# NIRGM_V8.net
KiCad netlist of a schematic drawn in EAGLE
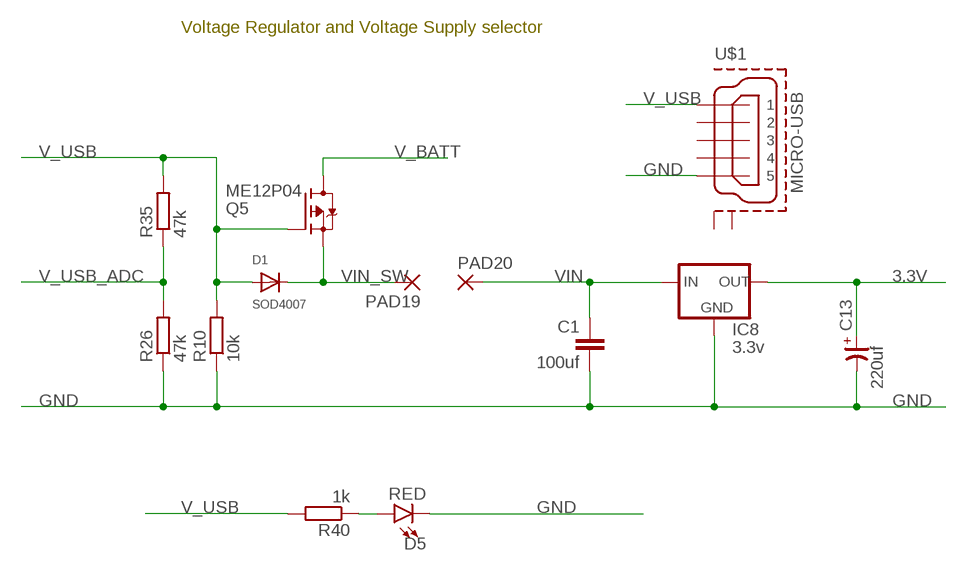
[diagram p0: schematic, sheet 1]
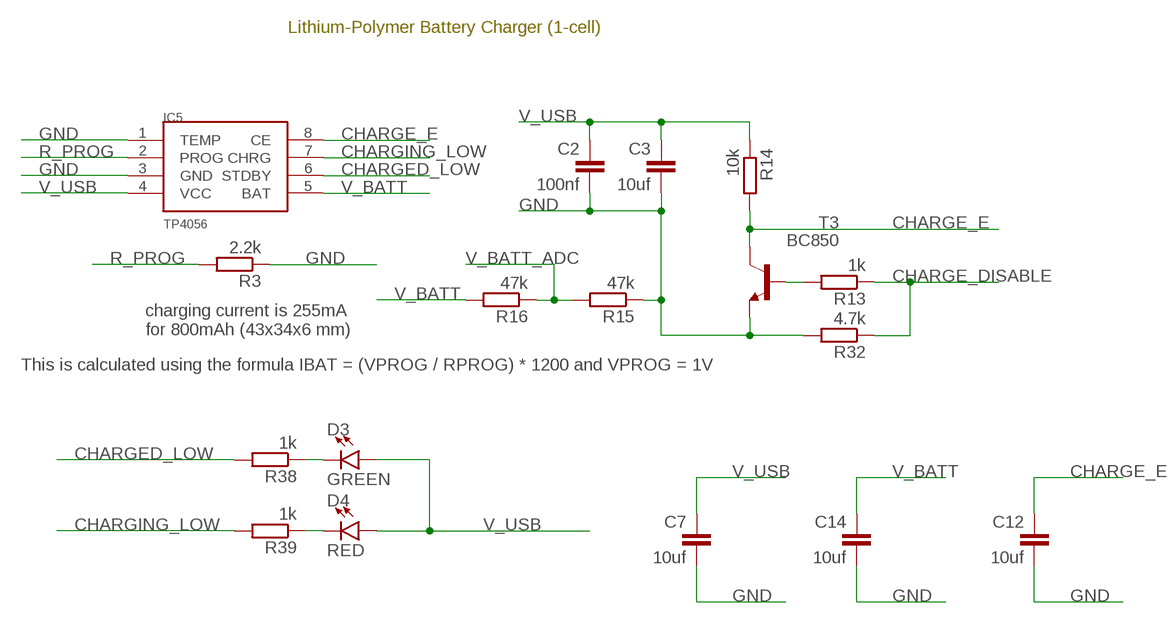
[diagram p1: schematic, sheet 2]
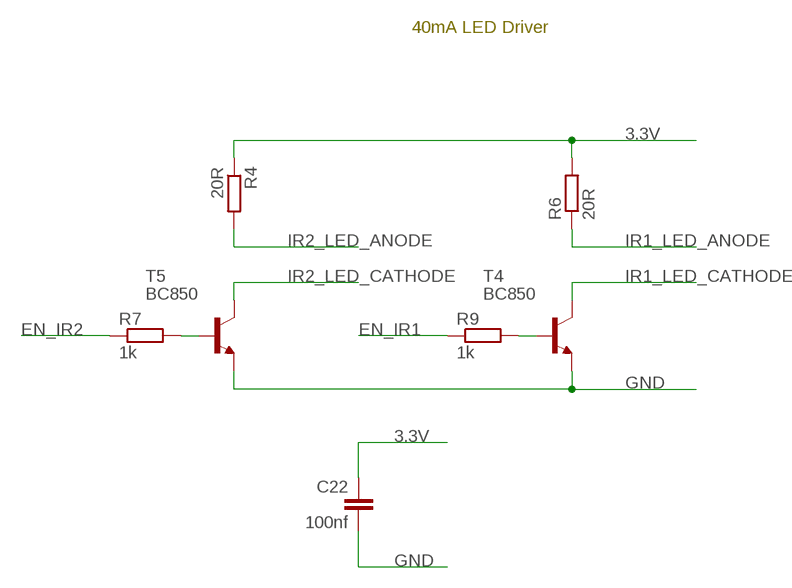
[diagram p2: schematic, sheet 3]
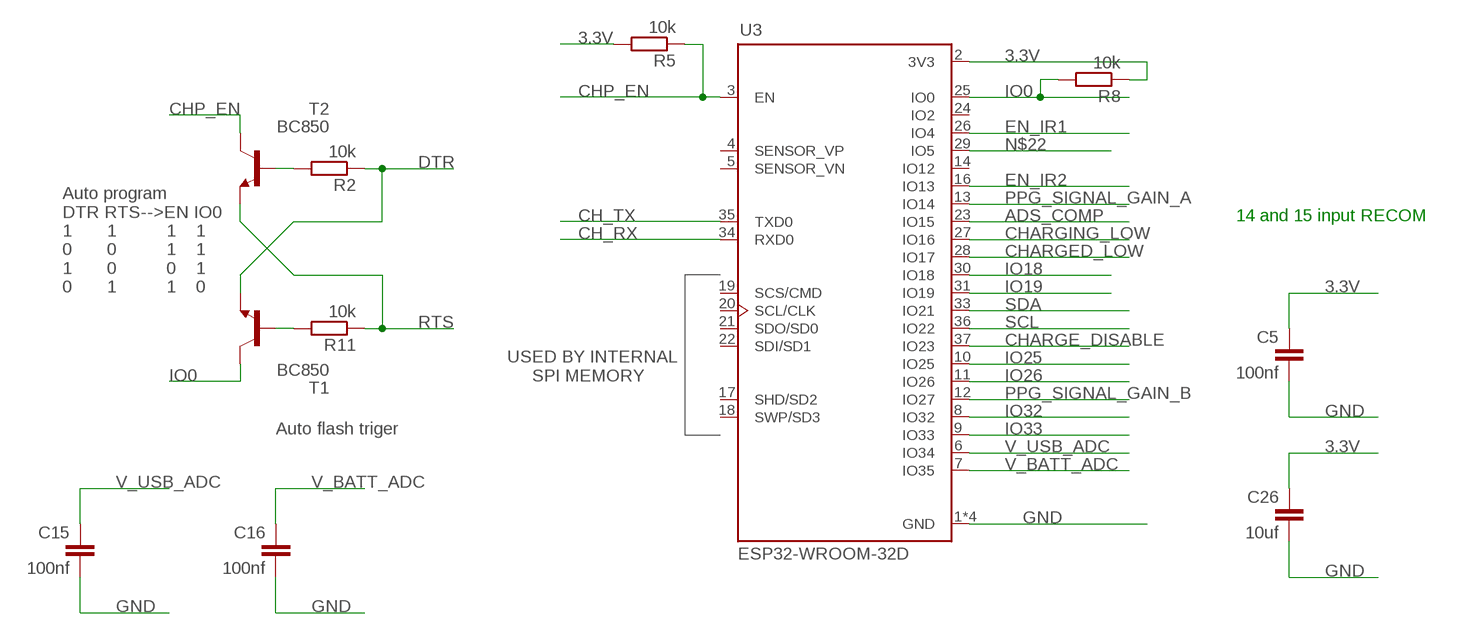
[diagram p3: schematic, sheet 4]
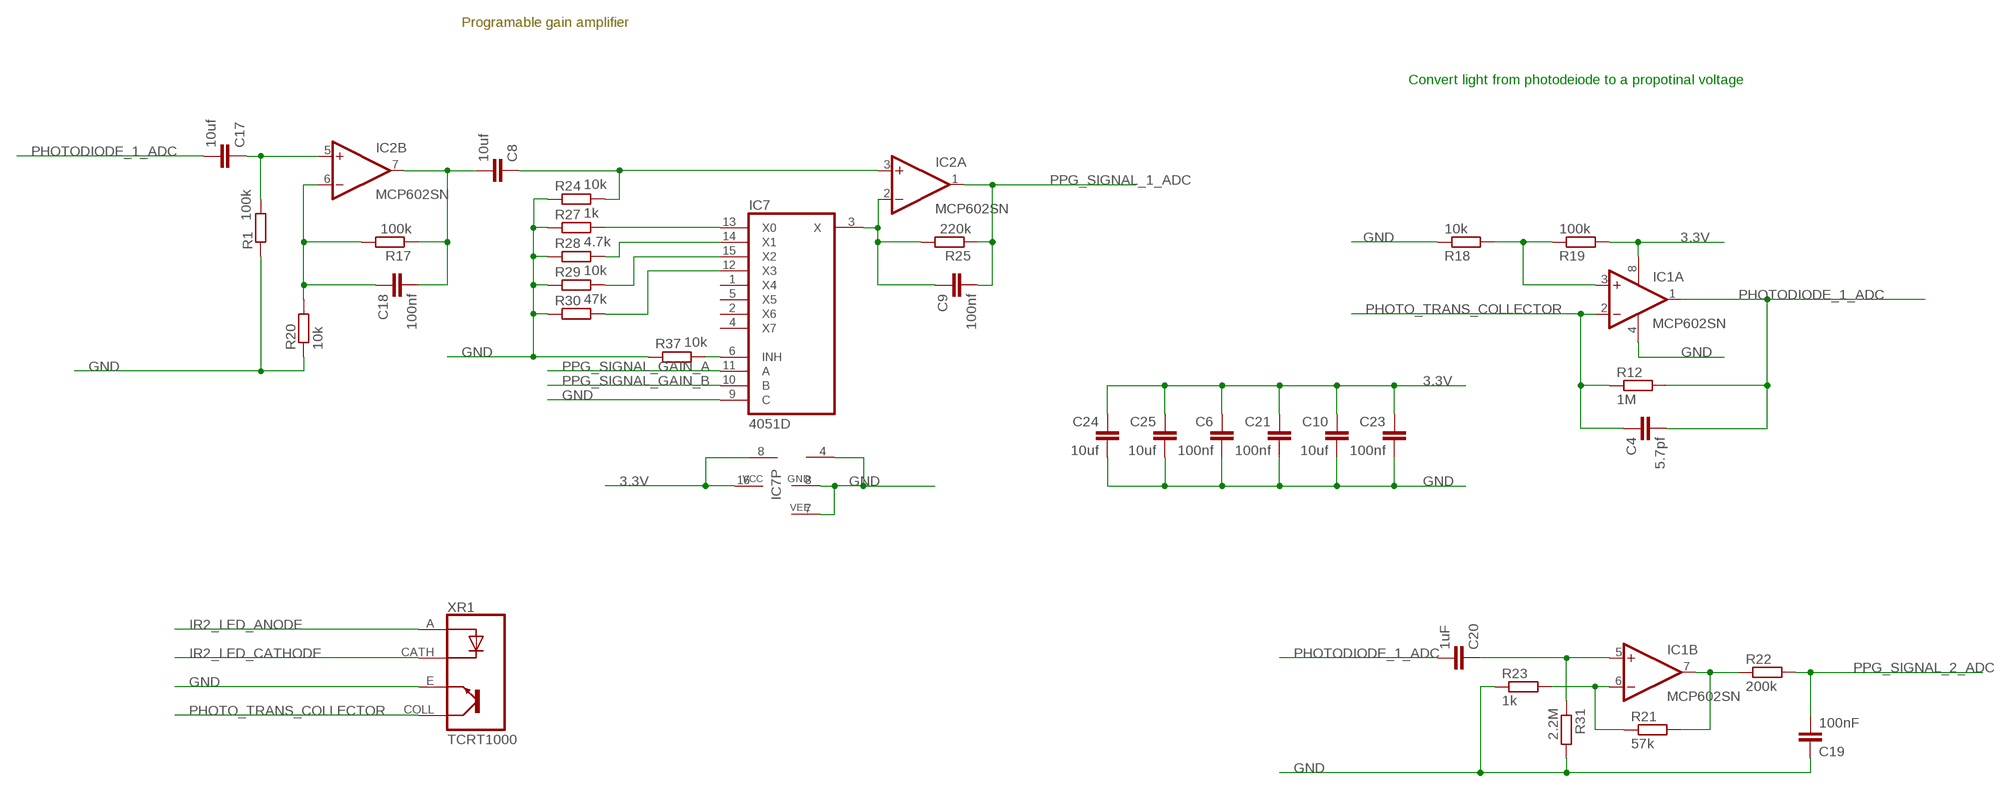
[diagram p4: schematic, sheet 5]
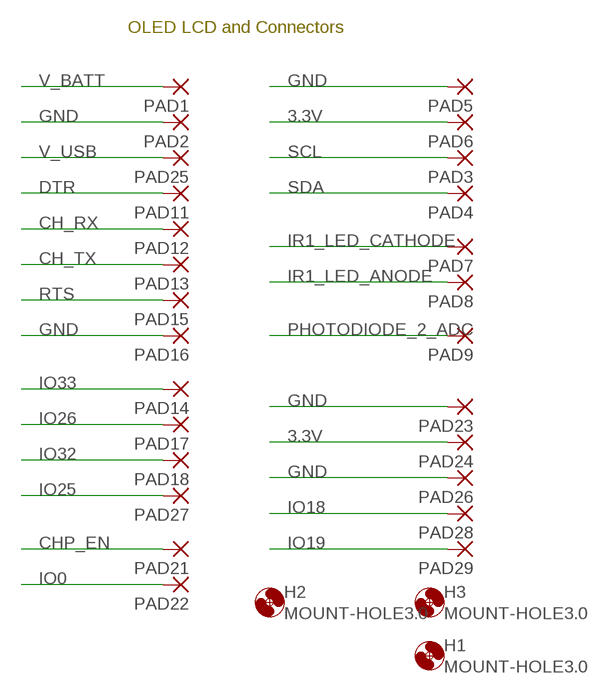
[diagram p5: schematic, sheet 6]
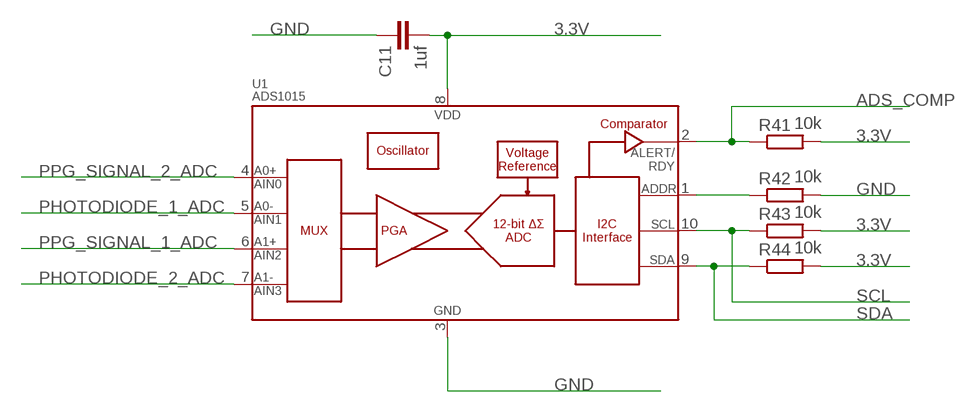
[diagram p6: schematic, sheet 7]

(export (version "E")
  (design (tool "Eeschema 10.0.6"))
  (components
    (comp (ref "C5")
      (value "100nf")
      (footprint "eagle-import:C1206K")
      (libsource (lib "eagle-import") (part "C-EUC1206K"))
    )
    (comp (ref "C15")
      (value "100nf")
      (footprint "eagle-import:C1206K")
      (libsource (lib "eagle-import") (part "C-EUC1206K"))
    )
    (comp (ref "C16")
      (value "100nf")
      (footprint "eagle-import:C1206K")
      (libsource (lib "eagle-import") (part "C-EUC1206K"))
    )
    (comp (ref "C26")
      (value "10uf")
      (footprint "eagle-import:C1206K")
      (libsource (lib "eagle-import") (part "C-EUC1206K"))
    )
    (comp (ref "R2")
      (value "10k")
      (footprint "eagle-import:R1206")
      (libsource (lib "eagle-import") (part "R-EU_R1206"))
    )
    (comp (ref "R5")
      (value "10k")
      (footprint "eagle-import:R1206")
      (libsource (lib "eagle-import") (part "R-EU_R1206"))
    )
    (comp (ref "R8")
      (value "10k")
      (footprint "eagle-import:R1206")
      (libsource (lib "eagle-import") (part "R-EU_R1206"))
    )
    (comp (ref "R11")
      (value "10k")
      (footprint "eagle-import:R1206")
      (libsource (lib "eagle-import") (part "R-EU_R1206"))
    )
    (comp (ref "T1")
      (value "BC850")
      (footprint "eagle-import:SOT23")
      (libsource (lib "eagle-import") (part "BC850"))
    )
    (comp (ref "T2")
      (value "BC850")
      (footprint "eagle-import:SOT23")
      (libsource (lib "eagle-import") (part "BC850"))
    )
    (comp (ref "U3")
      (value "ESP32-WROOM-32D")
      (footprint "eagle-import:MODULE_ESP32-WROOM-32D")
      (fields (field (name "MF") "Espressif Systems"))
      (libsource (lib "eagle-import") (part "ESP32-WROOM-32D"))
    )
    (comp (ref "C2")
      (value "100nf")
      (footprint "eagle-import:C1206K")
      (libsource (lib "eagle-import") (part "C-EUC1206K"))
    )
    (comp (ref "C3")
      (value "10uf")
      (footprint "eagle-import:C1206K")
      (libsource (lib "eagle-import") (part "C-EUC1206K"))
    )
    (comp (ref "C7")
      (value "10uf")
      (footprint "eagle-import:C1206K")
      (libsource (lib "eagle-import") (part "C-EUC1206K"))
    )
    (comp (ref "C12")
      (value "10uf")
      (footprint "eagle-import:C1206K")
      (libsource (lib "eagle-import") (part "C-EUC1206K"))
    )
    (comp (ref "C14")
      (value "10uf")
      (footprint "eagle-import:C1206K")
      (libsource (lib "eagle-import") (part "C-EUC1206K"))
    )
    (comp (ref "D3")
      (value "GREEN")
      (footprint "eagle-import:LED-1206")
      (libsource (lib "eagle-import") (part "LED-GREEN1206"))
    )
    (comp (ref "D4")
      (value "RED")
      (footprint "eagle-import:LED-1206")
      (libsource (lib "eagle-import") (part "LED-GREEN1206"))
    )
    (comp (ref "IC5")
      (value "TP4056")
      (footprint "eagle-import:SOP-8")
      (libsource (lib "eagle-import") (part "TP4056"))
    )
    (comp (ref "R3")
      (value "2.2k")
      (footprint "eagle-import:R1206")
      (libsource (lib "eagle-import") (part "R-EU_R1206"))
    )
    (comp (ref "R13")
      (value "1k")
      (footprint "eagle-import:R1206")
      (libsource (lib "eagle-import") (part "R-EU_R1206"))
    )
    (comp (ref "R14")
      (value "10k")
      (footprint "eagle-import:R1206")
      (libsource (lib "eagle-import") (part "R-EU_R1206"))
    )
    (comp (ref "R15")
      (value "47k")
      (footprint "eagle-import:R1206")
      (libsource (lib "eagle-import") (part "R-EU_R1206"))
    )
    (comp (ref "R16")
      (value "47k")
      (footprint "eagle-import:R1206")
      (libsource (lib "eagle-import") (part "R-EU_R1206"))
    )
    (comp (ref "R32")
      (value "4.7k")
      (footprint "eagle-import:R1206")
      (libsource (lib "eagle-import") (part "R-EU_R1206"))
    )
    (comp (ref "R38")
      (value "1k")
      (footprint "eagle-import:R1206")
      (libsource (lib "eagle-import") (part "R-EU_R1206"))
    )
    (comp (ref "R39")
      (value "1k")
      (footprint "eagle-import:R1206")
      (libsource (lib "eagle-import") (part "R-EU_R1206"))
    )
    (comp (ref "T3")
      (value "BC850")
      (footprint "eagle-import:SOT23")
      (libsource (lib "eagle-import") (part "BC850"))
    )
    (comp (ref "H1")
      (value "MOUNT-HOLE3.0")
      (footprint "eagle-import:3,0")
      (libsource (lib "eagle-import") (part "MOUNT-HOLE3.0"))
    )
    (comp (ref "H2")
      (value "MOUNT-HOLE3.0")
      (footprint "eagle-import:3,0")
      (libsource (lib "eagle-import") (part "MOUNT-HOLE3.0"))
    )
    (comp (ref "H3")
      (value "MOUNT-HOLE3.0")
      (footprint "eagle-import:3,0")
      (libsource (lib "eagle-import") (part "MOUNT-HOLE3.0"))
    )
    (comp (ref "PAD1")
      (value "WIREPADSMD5-2,5")
      (footprint "eagle-import:5-2,5")
      (libsource (lib "eagle-import") (part "WIREPADSMD5-2,5"))
    )
    (comp (ref "PAD2")
      (value "WIREPADSMD5-2,5")
      (footprint "eagle-import:5-2,5")
      (libsource (lib "eagle-import") (part "WIREPADSMD5-2,5"))
    )
    (comp (ref "PAD3")
      (value "SMD2")
      (footprint "eagle-import:SMD1,27-2,54")
      (libsource (lib "eagle-import") (part "SMD2"))
    )
    (comp (ref "PAD4")
      (value "SMD2")
      (footprint "eagle-import:SMD1,27-2,54")
      (libsource (lib "eagle-import") (part "SMD2"))
    )
    (comp (ref "PAD5")
      (value "SMD2")
      (footprint "eagle-import:SMD1,27-2,54")
      (libsource (lib "eagle-import") (part "SMD2"))
    )
    (comp (ref "PAD6")
      (value "SMD2")
      (footprint "eagle-import:SMD1,27-2,54")
      (libsource (lib "eagle-import") (part "SMD2"))
    )
    (comp (ref "PAD7")
      (value "SMD2")
      (footprint "eagle-import:SMD1,27-2,54")
      (libsource (lib "eagle-import") (part "SMD2"))
    )
    (comp (ref "PAD8")
      (value "SMD2")
      (footprint "eagle-import:SMD1,27-2,54")
      (libsource (lib "eagle-import") (part "SMD2"))
    )
    (comp (ref "PAD9")
      (value "SMD2")
      (footprint "eagle-import:SMD1,27-2,54")
      (libsource (lib "eagle-import") (part "SMD2"))
    )
    (comp (ref "PAD11")
      (value "SMD2")
      (footprint "eagle-import:SMD1,27-2,54")
      (libsource (lib "eagle-import") (part "SMD2"))
    )
    (comp (ref "PAD12")
      (value "SMD2")
      (footprint "eagle-import:SMD1,27-2,54")
      (libsource (lib "eagle-import") (part "SMD2"))
    )
    (comp (ref "PAD13")
      (value "SMD2")
      (footprint "eagle-import:SMD1,27-2,54")
      (libsource (lib "eagle-import") (part "SMD2"))
    )
    (comp (ref "PAD14")
      (value "SMD2")
      (footprint "eagle-import:SMD1,27-2,54")
      (libsource (lib "eagle-import") (part "SMD2"))
    )
    (comp (ref "PAD15")
      (value "SMD2")
      (footprint "eagle-import:SMD1,27-2,54")
      (libsource (lib "eagle-import") (part "SMD2"))
    )
    (comp (ref "PAD16")
      (value "SMD2")
      (footprint "eagle-import:SMD1,27-2,54")
      (libsource (lib "eagle-import") (part "SMD2"))
    )
    (comp (ref "PAD17")
      (value "SMD2")
      (footprint "eagle-import:SMD1,27-2,54")
      (libsource (lib "eagle-import") (part "SMD2"))
    )
    (comp (ref "PAD18")
      (value "SMD2")
      (footprint "eagle-import:SMD1,27-2,54")
      (libsource (lib "eagle-import") (part "SMD2"))
    )
    (comp (ref "PAD21")
      (value "SMD2")
      (footprint "eagle-import:SMD1,27-2,54")
      (libsource (lib "eagle-import") (part "SMD2"))
    )
    (comp (ref "PAD22")
      (value "SMD2")
      (footprint "eagle-import:SMD1,27-2,54")
      (libsource (lib "eagle-import") (part "SMD2"))
    )
    (comp (ref "PAD23")
      (value "SMD2")
      (footprint "eagle-import:SMD1,27-2,54")
      (libsource (lib "eagle-import") (part "SMD2"))
    )
    (comp (ref "PAD24")
      (value "SMD2")
      (footprint "eagle-import:SMD1,27-2,54")
      (libsource (lib "eagle-import") (part "SMD2"))
    )
    (comp (ref "PAD25")
      (value "SMD2")
      (footprint "eagle-import:SMD1,27-2,54")
      (libsource (lib "eagle-import") (part "SMD2"))
    )
    (comp (ref "PAD26")
      (value "SMD2")
      (footprint "eagle-import:SMD1,27-2,54")
      (libsource (lib "eagle-import") (part "SMD2"))
    )
    (comp (ref "PAD27")
      (value "SMD2")
      (footprint "eagle-import:SMD1,27-2,54")
      (libsource (lib "eagle-import") (part "SMD2"))
    )
    (comp (ref "PAD28")
      (value "SMD2")
      (footprint "eagle-import:SMD1,27-2,54")
      (libsource (lib "eagle-import") (part "SMD2"))
    )
    (comp (ref "PAD29")
      (value "SMD2")
      (footprint "eagle-import:SMD1,27-2,54")
      (libsource (lib "eagle-import") (part "SMD2"))
    )
    (comp (ref "C4")
      (value "5.7pf")
      (footprint "eagle-import:C1206K")
      (libsource (lib "eagle-import") (part "C-EUC1206K"))
    )
    (comp (ref "C6")
      (value "100nf")
      (footprint "eagle-import:C1206K")
      (libsource (lib "eagle-import") (part "C-EUC1206K"))
    )
    (comp (ref "C8")
      (value "10uf")
      (footprint "eagle-import:C1206K")
      (libsource (lib "eagle-import") (part "C-EUC1206K"))
    )
    (comp (ref "C9")
      (value "100nf")
      (footprint "eagle-import:C1206K")
      (libsource (lib "eagle-import") (part "C-EUC1206K"))
    )
    (comp (ref "C10")
      (value "10uf")
      (footprint "eagle-import:C1206K")
      (libsource (lib "eagle-import") (part "C-EUC1206K"))
    )
    (comp (ref "C17")
      (value "10uf")
      (footprint "eagle-import:C1206K")
      (libsource (lib "eagle-import") (part "C-EUC1206K"))
    )
    (comp (ref "C18")
      (value "100nf")
      (footprint "eagle-import:C1206K")
      (libsource (lib "eagle-import") (part "C-EUC1206K"))
    )
    (comp (ref "C19")
      (value "100nF")
      (footprint "eagle-import:C1206K")
      (libsource (lib "eagle-import") (part "C-EUC1206K"))
    )
    (comp (ref "C20")
      (value "1uF")
      (footprint "eagle-import:C1206K")
      (libsource (lib "eagle-import") (part "C-EUC1206K"))
    )
    (comp (ref "C21")
      (value "100nf")
      (footprint "eagle-import:C1206K")
      (libsource (lib "eagle-import") (part "C-EUC1206K"))
    )
    (comp (ref "C23")
      (value "100nf")
      (footprint "eagle-import:C1206K")
      (libsource (lib "eagle-import") (part "C-EUC1206K"))
    )
    (comp (ref "C24")
      (value "10uf")
      (footprint "eagle-import:C1206K")
      (libsource (lib "eagle-import") (part "C-EUC1206K"))
    )
    (comp (ref "C25")
      (value "10uf")
      (footprint "eagle-import:C1206K")
      (libsource (lib "eagle-import") (part "C-EUC1206K"))
    )
    (comp (ref "IC1")
      (value "MCP602SN")
      (footprint "eagle-import:SO08")
      (libsource (lib "eagle-import") (part "linear_262_MCP602SN"))
    )
    (comp (ref "IC2")
      (value "MCP602SN")
      (footprint "eagle-import:SO08")
      (libsource (lib "eagle-import") (part "MCP602SN"))
    )
    (comp (ref "IC7")
      (value "4051D")
      (footprint "eagle-import:SO16")
      (libsource (lib "eagle-import") (part "4051D"))
    )
    (comp (ref "R1")
      (value "100k")
      (footprint "eagle-import:R1206")
      (libsource (lib "eagle-import") (part "R-EU_R1206"))
    )
    (comp (ref "R12")
      (value "1M")
      (footprint "eagle-import:R1206")
      (libsource (lib "eagle-import") (part "R-EU_R1206"))
    )
    (comp (ref "R17")
      (value "100k")
      (footprint "eagle-import:R1206")
      (libsource (lib "eagle-import") (part "R-EU_R1206"))
    )
    (comp (ref "R18")
      (value "10k")
      (footprint "eagle-import:R1206")
      (libsource (lib "eagle-import") (part "R-EU_R1206"))
    )
    (comp (ref "R19")
      (value "100k")
      (footprint "eagle-import:R1206")
      (libsource (lib "eagle-import") (part "R-EU_R1206"))
    )
    (comp (ref "R20")
      (value "10k")
      (footprint "eagle-import:R1206")
      (libsource (lib "eagle-import") (part "R-EU_R1206"))
    )
    (comp (ref "R21")
      (value "57k")
      (footprint "eagle-import:R1206")
      (libsource (lib "eagle-import") (part "R-EU_R1206"))
    )
    (comp (ref "R22")
      (value "200k")
      (footprint "eagle-import:R1206")
      (libsource (lib "eagle-import") (part "R-EU_R1206"))
    )
    (comp (ref "R23")
      (value "1k")
      (footprint "eagle-import:R1206")
      (libsource (lib "eagle-import") (part "R-EU_R1206"))
    )
    (comp (ref "R24")
      (value "10k")
      (footprint "eagle-import:R1206")
      (libsource (lib "eagle-import") (part "R-EU_R1206"))
    )
    (comp (ref "R25")
      (value "220k")
      (footprint "eagle-import:R1206")
      (libsource (lib "eagle-import") (part "R-EU_R1206"))
    )
    (comp (ref "R27")
      (value "1k")
      (footprint "eagle-import:R1206")
      (libsource (lib "eagle-import") (part "R-EU_R1206"))
    )
    (comp (ref "R28")
      (value "4.7k")
      (footprint "eagle-import:R1206")
      (libsource (lib "eagle-import") (part "R-EU_R1206"))
    )
    (comp (ref "R29")
      (value "10k")
      (footprint "eagle-import:R1206")
      (libsource (lib "eagle-import") (part "R-EU_R1206"))
    )
    (comp (ref "R30")
      (value "47k")
      (footprint "eagle-import:R1206")
      (libsource (lib "eagle-import") (part "R-EU_R1206"))
    )
    (comp (ref "R31")
      (value "2.2M")
      (footprint "eagle-import:R1206")
      (libsource (lib "eagle-import") (part "R-EU_R1206"))
    )
    (comp (ref "R37")
      (value "10k")
      (footprint "eagle-import:R1206")
      (libsource (lib "eagle-import") (part "R-EU_R1206"))
    )
    (comp (ref "XR1")
      (value "TCRT1000")
      (footprint "eagle-import:XDCR_TCRT1000")
      (fields (field (name "MF") "Vishay"))
      (libsource (lib "eagle-import") (part "TCRT1000"))
    )
    (comp (ref "C22")
      (value "100nf")
      (footprint "eagle-import:C1206K")
      (libsource (lib "eagle-import") (part "C-EUC1206K"))
    )
    (comp (ref "R4")
      (value "20R")
      (footprint "eagle-import:R1206")
      (libsource (lib "eagle-import") (part "R-EU_R1206"))
    )
    (comp (ref "R6")
      (value "20R")
      (footprint "eagle-import:R1206")
      (libsource (lib "eagle-import") (part "R-EU_R1206"))
    )
    (comp (ref "R7")
      (value "1k")
      (footprint "eagle-import:R1206")
      (libsource (lib "eagle-import") (part "R-EU_R1206"))
    )
    (comp (ref "R9")
      (value "1k")
      (footprint "eagle-import:R1206")
      (libsource (lib "eagle-import") (part "R-EU_R1206"))
    )
    (comp (ref "T4")
      (value "BC850")
      (footprint "eagle-import:SOT23")
      (libsource (lib "eagle-import") (part "BC850"))
    )
    (comp (ref "T5")
      (value "BC850")
      (footprint "eagle-import:SOT23")
      (libsource (lib "eagle-import") (part "BC850"))
    )
    (comp (ref "C11")
      (value "1uf")
      (footprint "eagle-import:C1206K")
      (libsource (lib "eagle-import") (part "C-EUC1206K"))
    )
    (comp (ref "R41")
      (value "10k")
      (footprint "eagle-import:R1206")
      (libsource (lib "eagle-import") (part "R-EU_R1206"))
    )
    (comp (ref "R42")
      (value "10k")
      (footprint "eagle-import:R1206")
      (libsource (lib "eagle-import") (part "R-EU_R1206"))
    )
    (comp (ref "R43")
      (value "10k")
      (footprint "eagle-import:R1206")
      (libsource (lib "eagle-import") (part "R-EU_R1206"))
    )
    (comp (ref "R44")
      (value "10k")
      (footprint "eagle-import:R1206")
      (libsource (lib "eagle-import") (part "R-EU_R1206"))
    )
    (comp (ref "U1")
      (value "ADS1015")
      (footprint "eagle-import:MSOP10")
      (libsource (lib "eagle-import") (part "ADS1015"))
    )
    (comp (ref "C1")
      (value "100uf")
      (footprint "eagle-import:C1206K")
      (libsource (lib "eagle-import") (part "C-EUC1206K"))
    )
    (comp (ref "C13")
      (value "220uf")
      (footprint "eagle-import:7343_T")
      (libsource (lib "eagle-import") (part "CP-7343"))
    )
    (comp (ref "D1")
      (value "SOD4007")
      (footprint "eagle-import:SOD-123FL")
      (libsource (lib "eagle-import") (part "DIODE_SOD-123FL"))
    )
    (comp (ref "D5")
      (value "RED")
      (footprint "eagle-import:LED-1206")
      (libsource (lib "eagle-import") (part "LED-GREEN1206"))
    )
    (comp (ref "IC8")
      (value "3.3v")
      (footprint "eagle-import:TO252")
      (libsource (lib "eagle-import") (part "LM1117TO252"))
    )
    (comp (ref "PAD19")
      (value "SMD2")
      (footprint "eagle-import:SMD1,27-2,54")
      (libsource (lib "eagle-import") (part "SMD2"))
    )
    (comp (ref "PAD20")
      (value "SMD2")
      (footprint "eagle-import:SMD1,27-2,54")
      (libsource (lib "eagle-import") (part "SMD2"))
    )
    (comp (ref "Q5")
      (value "ME12P04")
      (footprint "eagle-import:TO252")
      (libsource (lib "eagle-import") (part "FDD4141TO252"))
    )
    (comp (ref "R10")
      (value "10k")
      (footprint "eagle-import:R1206")
      (libsource (lib "eagle-import") (part "R-EU_R1206"))
    )
    (comp (ref "R26")
      (value "47k")
      (footprint "eagle-import:R1206")
      (libsource (lib "eagle-import") (part "R-EU_R1206"))
    )
    (comp (ref "R35")
      (value "47k")
      (footprint "eagle-import:R1206")
      (libsource (lib "eagle-import") (part "R-EU_R1206"))
    )
    (comp (ref "R40")
      (value "1k")
      (footprint "eagle-import:R1206")
      (libsource (lib "eagle-import") (part "R-EU_R1206"))
    )
    (comp (ref "U$1")
      (value "MICRO-USB")
      (footprint "eagle-import:47589-0001")
      (libsource (lib "eagle-import") (part "MICRO-USB-RECEPTACLE47589-0001"))
    )
  )
  (nets
    (net (code "1") (name "3.3V") (class "Default")
      (node (ref "C10") (pin "1") (pinfunction "1_1") (pintype "passive"))
      (node (ref "C11") (pin "2") (pinfunction "2_2") (pintype "passive"))
      (node (ref "C13") (pin "+") (pinfunction "+_+") (pintype "passive"))
      (node (ref "C21") (pin "1") (pinfunction "1_1") (pintype "passive"))
      (node (ref "C22") (pin "1") (pinfunction "1_1") (pintype "passive"))
      (node (ref "C23") (pin "1") (pinfunction "1_1") (pintype "passive"))
      (node (ref "C24") (pin "1") (pinfunction "1_1") (pintype "passive"))
      (node (ref "C25") (pin "1") (pinfunction "1_1") (pintype "passive"))
      (node (ref "C26") (pin "1") (pinfunction "1_1") (pintype "passive"))
      (node (ref "C5") (pin "1") (pinfunction "1_1") (pintype "passive"))
      (node (ref "C6") (pin "1") (pinfunction "1_1") (pintype "passive"))
      (node (ref "IC1") (pin "8") (pinfunction "V+_8") (pintype "power_in"))
      (node (ref "IC2") (pin "8") (pinfunction "V+_8") (pintype "power_in"))
      (node (ref "IC7") (pin "16") (pinfunction "VCC_16") (pintype "power_in"))
      (node (ref "IC8") (pin "3") (pinfunction "OUT_3") (pintype "passive"))
      (node (ref "PAD24") (pin "1") (pinfunction "P_1") (pintype "passive"))
      (node (ref "PAD6") (pin "1") (pinfunction "P_1") (pintype "passive"))
      (node (ref "R19") (pin "2") (pinfunction "2_2") (pintype "passive"))
      (node (ref "R4") (pin "1") (pinfunction "1_1") (pintype "passive"))
      (node (ref "R41") (pin "2") (pinfunction "2_2") (pintype "passive"))
      (node (ref "R43") (pin "2") (pinfunction "2_2") (pintype "passive"))
      (node (ref "R44") (pin "2") (pinfunction "2_2") (pintype "passive"))
      (node (ref "R5") (pin "2") (pinfunction "2_2") (pintype "passive"))
      (node (ref "R6") (pin "2") (pinfunction "2_2") (pintype "passive"))
      (node (ref "R8") (pin "1") (pinfunction "1_1") (pintype "passive"))
      (node (ref "U1") (pin "8") (pinfunction "VDD_8") (pintype "bidirectional"))
      (node (ref "U3") (pin "2") (pinfunction "3V3_2") (pintype "power_in"))
    )
    (net (code "2") (name "ADS_COMP") (class "Default")
      (node (ref "R41") (pin "1") (pinfunction "1_1") (pintype "passive"))
      (node (ref "U1") (pin "2") (pinfunction "ALERT/RDY_2") (pintype "bidirectional"))
      (node (ref "U3") (pin "23") (pinfunction "IO15_23") (pintype "bidirectional"))
    )
    (net (code "3") (name "CHARGED_LOW") (class "Default")
      (node (ref "IC5") (pin "6") (pinfunction "STDBY_6") (pintype "bidirectional"))
      (node (ref "R38") (pin "2") (pinfunction "2_2") (pintype "passive"))
      (node (ref "U3") (pin "28") (pinfunction "IO17_28") (pintype "bidirectional"))
    )
    (net (code "4") (name "CHARGE_DISABLE") (class "Default")
      (node (ref "R13") (pin "1") (pinfunction "1_1") (pintype "passive"))
      (node (ref "R32") (pin "1") (pinfunction "1_1") (pintype "passive"))
      (node (ref "U3") (pin "37") (pinfunction "IO23_37") (pintype "bidirectional"))
    )
    (net (code "5") (name "CHARGE_E") (class "Default")
      (node (ref "C12") (pin "1") (pinfunction "1_1") (pintype "passive"))
      (node (ref "IC5") (pin "8") (pinfunction "CE_8") (pintype "bidirectional"))
      (node (ref "R14") (pin "2") (pinfunction "2_2") (pintype "passive"))
      (node (ref "T3") (pin "3") (pinfunction "C_3") (pintype "passive"))
    )
    (net (code "6") (name "CHARGING_LOW") (class "Default")
      (node (ref "IC5") (pin "7") (pinfunction "CHRG_7") (pintype "bidirectional"))
      (node (ref "R39") (pin "2") (pinfunction "2_2") (pintype "passive"))
      (node (ref "U3") (pin "27") (pinfunction "IO16_27") (pintype "bidirectional"))
    )
    (net (code "7") (name "CHP_EN") (class "Default")
      (node (ref "PAD21") (pin "1") (pinfunction "P_1") (pintype "passive"))
      (node (ref "R5") (pin "1") (pinfunction "1_1") (pintype "passive"))
      (node (ref "T2") (pin "3") (pinfunction "C_3") (pintype "passive"))
      (node (ref "U3") (pin "3") (pinfunction "EN_3") (pintype "input"))
    )
    (net (code "8") (name "CH_RX") (class "Default")
      (node (ref "PAD12") (pin "1") (pinfunction "P_1") (pintype "passive"))
      (node (ref "U3") (pin "34") (pinfunction "RXD0_34") (pintype "bidirectional"))
    )
    (net (code "9") (name "CH_TX") (class "Default")
      (node (ref "PAD13") (pin "1") (pinfunction "P_1") (pintype "passive"))
      (node (ref "U3") (pin "35") (pinfunction "TXD0_35") (pintype "bidirectional"))
    )
    (net (code "10") (name "DTR") (class "Default")
      (node (ref "PAD11") (pin "1") (pinfunction "P_1") (pintype "passive"))
      (node (ref "R2") (pin "1") (pinfunction "1_1") (pintype "passive"))
      (node (ref "T1") (pin "2") (pinfunction "E_2") (pintype "passive"))
    )
    (net (code "11") (name "EN_IR1") (class "Default")
      (node (ref "R9") (pin "1") (pinfunction "1_1") (pintype "passive"))
      (node (ref "U3") (pin "26") (pinfunction "IO4_26") (pintype "bidirectional"))
    )
    (net (code "12") (name "EN_IR2") (class "Default")
      (node (ref "R7") (pin "1") (pinfunction "1_1") (pintype "passive"))
      (node (ref "U3") (pin "16") (pinfunction "IO13_16") (pintype "bidirectional"))
    )
    (net (code "13") (name "GND") (class "Default")
      (node (ref "C1") (pin "2") (pinfunction "2_2") (pintype "passive"))
      (node (ref "C10") (pin "2") (pinfunction "2_2") (pintype "passive"))
      (node (ref "C11") (pin "1") (pinfunction "1_1") (pintype "passive"))
      (node (ref "C12") (pin "2") (pinfunction "2_2") (pintype "passive"))
      (node (ref "C13") (pin "-") (pinfunction "-_-") (pintype "passive"))
      (node (ref "C14") (pin "2") (pinfunction "2_2") (pintype "passive"))
      (node (ref "C15") (pin "2") (pinfunction "2_2") (pintype "passive"))
      (node (ref "C16") (pin "2") (pinfunction "2_2") (pintype "passive"))
      (node (ref "C19") (pin "1") (pinfunction "1_1") (pintype "passive"))
      (node (ref "C2") (pin "2") (pinfunction "2_2") (pintype "passive"))
      (node (ref "C21") (pin "2") (pinfunction "2_2") (pintype "passive"))
      (node (ref "C22") (pin "2") (pinfunction "2_2") (pintype "passive"))
      (node (ref "C23") (pin "2") (pinfunction "2_2") (pintype "passive"))
      (node (ref "C24") (pin "2") (pinfunction "2_2") (pintype "passive"))
      (node (ref "C25") (pin "2") (pinfunction "2_2") (pintype "passive"))
      (node (ref "C26") (pin "2") (pinfunction "2_2") (pintype "passive"))
      (node (ref "C3") (pin "2") (pinfunction "2_2") (pintype "passive"))
      (node (ref "C5") (pin "2") (pinfunction "2_2") (pintype "passive"))
      (node (ref "C6") (pin "2") (pinfunction "2_2") (pintype "passive"))
      (node (ref "C7") (pin "2") (pinfunction "2_2") (pintype "passive"))
      (node (ref "D5") (pin "C") (pinfunction "C_C") (pintype "passive"))
      (node (ref "IC1") (pin "4") (pinfunction "V-_4") (pintype "power_in"))
      (node (ref "IC2") (pin "4") (pinfunction "V-_4") (pintype "power_in"))
      (node (ref "IC5") (pin "1") (pinfunction "TEMP_1") (pintype "bidirectional"))
      (node (ref "IC5") (pin "3") (pinfunction "GND_3") (pintype "bidirectional"))
      (node (ref "IC7") (pin "7") (pinfunction "VEE_7") (pintype "power_in"))
      (node (ref "IC7") (pin "8") (pinfunction "GND_8") (pintype "power_in"))
      (node (ref "IC7") (pin "9") (pinfunction "C_9") (pintype "input"))
      (node (ref "IC8") (pin "1") (pinfunction "GND_1") (pintype "input"))
      (node (ref "PAD16") (pin "1") (pinfunction "P_1") (pintype "passive"))
      (node (ref "PAD2") (pin "1") (pinfunction "P_1") (pintype "passive"))
      (node (ref "PAD23") (pin "1") (pinfunction "P_1") (pintype "passive"))
      (node (ref "PAD26") (pin "1") (pinfunction "P_1") (pintype "passive"))
      (node (ref "PAD5") (pin "1") (pinfunction "P_1") (pintype "passive"))
      (node (ref "R1") (pin "1") (pinfunction "1_1") (pintype "passive"))
      (node (ref "R10") (pin "1") (pinfunction "1_1") (pintype "passive"))
      (node (ref "R15") (pin "1") (pinfunction "1_1") (pintype "passive"))
      (node (ref "R18") (pin "1") (pinfunction "1_1") (pintype "passive"))
      (node (ref "R20") (pin "1") (pinfunction "1_1") (pintype "passive"))
      (node (ref "R23") (pin "1") (pinfunction "1_1") (pintype "passive"))
      (node (ref "R24") (pin "1") (pinfunction "1_1") (pintype "passive"))
      (node (ref "R26") (pin "1") (pinfunction "1_1") (pintype "passive"))
      (node (ref "R27") (pin "1") (pinfunction "1_1") (pintype "passive"))
      (node (ref "R28") (pin "1") (pinfunction "1_1") (pintype "passive"))
      (node (ref "R29") (pin "1") (pinfunction "1_1") (pintype "passive"))
      (node (ref "R3") (pin "1") (pinfunction "1_1") (pintype "passive"))
      (node (ref "R30") (pin "1") (pinfunction "1_1") (pintype "passive"))
      (node (ref "R31") (pin "2") (pinfunction "2_2") (pintype "passive"))
      (node (ref "R32") (pin "2") (pinfunction "2_2") (pintype "passive"))
      (node (ref "R37") (pin "1") (pinfunction "1_1") (pintype "passive"))
      (node (ref "R42") (pin "2") (pinfunction "2_2") (pintype "passive"))
      (node (ref "T3") (pin "2") (pinfunction "E_2") (pintype "passive"))
      (node (ref "T4") (pin "2") (pinfunction "E_2") (pintype "passive"))
      (node (ref "T5") (pin "2") (pinfunction "E_2") (pintype "passive"))
      (node (ref "U$1") (pin "5") (pinfunction "5_5") (pintype "input"))
      (node (ref "U1") (pin "3") (pinfunction "VSS_3") (pintype "bidirectional"))
      (node (ref "U3") (pin "1") (pinfunction "GND_1") (pintype "power_in"))
      (node (ref "U3") (pin "15") (pinfunction "GND_15") (pintype "power_in"))
      (node (ref "U3") (pin "38") (pinfunction "GND_38") (pintype "power_in"))
      (node (ref "U3") (pin "39") (pinfunction "GND_39") (pintype "power_in"))
      (node (ref "XR1") (pin "E") (pinfunction "E_E") (pintype "passive"))
    )
    (net (code "14") (name "IO0") (class "Default")
      (node (ref "PAD22") (pin "1") (pinfunction "P_1") (pintype "passive"))
      (node (ref "R8") (pin "2") (pinfunction "2_2") (pintype "passive"))
      (node (ref "T1") (pin "3") (pinfunction "C_3") (pintype "passive"))
      (node (ref "U3") (pin "25") (pinfunction "IO0_25") (pintype "bidirectional"))
    )
    (net (code "15") (name "IO18") (class "Default")
      (node (ref "PAD28") (pin "1") (pinfunction "P_1") (pintype "passive"))
      (node (ref "U3") (pin "30") (pinfunction "IO18_30") (pintype "bidirectional"))
    )
    (net (code "16") (name "IO19") (class "Default")
      (node (ref "PAD29") (pin "1") (pinfunction "P_1") (pintype "passive"))
      (node (ref "U3") (pin "31") (pinfunction "IO19_31") (pintype "bidirectional"))
    )
    (net (code "17") (name "IO25") (class "Default")
      (node (ref "PAD27") (pin "1") (pinfunction "P_1") (pintype "passive"))
      (node (ref "U3") (pin "10") (pinfunction "IO25_10") (pintype "bidirectional"))
    )
    (net (code "18") (name "IO26") (class "Default")
      (node (ref "PAD17") (pin "1") (pinfunction "P_1") (pintype "passive"))
      (node (ref "U3") (pin "11") (pinfunction "IO26_11") (pintype "bidirectional"))
    )
    (net (code "19") (name "IO32") (class "Default")
      (node (ref "PAD18") (pin "1") (pinfunction "P_1") (pintype "passive"))
      (node (ref "U3") (pin "8") (pinfunction "IO32_8") (pintype "bidirectional"))
    )
    (net (code "20") (name "IO33") (class "Default")
      (node (ref "PAD14") (pin "1") (pinfunction "P_1") (pintype "passive"))
      (node (ref "U3") (pin "9") (pinfunction "IO33_9") (pintype "bidirectional"))
    )
    (net (code "21") (name "IR1_LED_ANODE") (class "Default")
      (node (ref "PAD8") (pin "1") (pinfunction "P_1") (pintype "passive"))
      (node (ref "R6") (pin "1") (pinfunction "1_1") (pintype "passive"))
    )
    (net (code "22") (name "IR1_LED_CATHODE") (class "Default")
      (node (ref "PAD7") (pin "1") (pinfunction "P_1") (pintype "passive"))
      (node (ref "T4") (pin "3") (pinfunction "C_3") (pintype "passive"))
    )
    (net (code "23") (name "IR2_LED_ANODE") (class "Default")
      (node (ref "R4") (pin "2") (pinfunction "2_2") (pintype "passive"))
      (node (ref "XR1") (pin "A") (pinfunction "A_A") (pintype "passive"))
    )
    (net (code "24") (name "IR2_LED_CATHODE") (class "Default")
      (node (ref "T5") (pin "3") (pinfunction "C_3") (pintype "passive"))
      (node (ref "XR1") (pin "CATH") (pinfunction "C_CATH") (pintype "passive"))
    )
    (net (code "25") (name "N$22") (class "Default")
      (node (ref "U3") (pin "29") (pinfunction "IO5_29") (pintype "bidirectional"))
    )
    (net (code "26") (name "Net-(D3-PadC)") (class "Default")
      (node (ref "D3") (pin "C") (pinfunction "C_C") (pintype "passive"))
      (node (ref "R38") (pin "1") (pinfunction "1_1") (pintype "passive"))
    )
    (net (code "27") (name "Net-(D4-PadC)") (class "Default")
      (node (ref "D4") (pin "C") (pinfunction "C_C") (pintype "passive"))
      (node (ref "R39") (pin "1") (pinfunction "1_1") (pintype "passive"))
    )
    (net (code "28") (name "Net-(D5-PadA)") (class "Default")
      (node (ref "D5") (pin "A") (pinfunction "A_A") (pintype "passive"))
      (node (ref "R40") (pin "1") (pinfunction "1_1") (pintype "passive"))
    )
    (net (code "29") (name "Net-(IC1A-+IN)") (class "Default")
      (node (ref "IC1") (pin "3") (pinfunction "+IN_3") (pintype "input"))
      (node (ref "R18") (pin "2") (pinfunction "2_2") (pintype "passive"))
      (node (ref "R19") (pin "1") (pinfunction "1_1") (pintype "passive"))
    )
    (net (code "30") (name "Net-(IC1B-+IN)") (class "Default")
      (node (ref "C20") (pin "1") (pinfunction "1_1") (pintype "passive"))
      (node (ref "IC1") (pin "5") (pinfunction "+IN_5") (pintype "input"))
      (node (ref "R31") (pin "1") (pinfunction "1_1") (pintype "passive"))
    )
    (net (code "31") (name "Net-(IC1B--IN)") (class "Default")
      (node (ref "IC1") (pin "6") (pinfunction "-IN_6") (pintype "input"))
      (node (ref "R21") (pin "1") (pinfunction "1_1") (pintype "passive"))
      (node (ref "R23") (pin "2") (pinfunction "2_2") (pintype "passive"))
    )
    (net (code "32") (name "Net-(IC1B-OUT)") (class "Default")
      (node (ref "IC1") (pin "7") (pinfunction "OUT_7") (pintype "output"))
      (node (ref "R21") (pin "2") (pinfunction "2_2") (pintype "passive"))
      (node (ref "R22") (pin "1") (pinfunction "1_1") (pintype "passive"))
    )
    (net (code "33") (name "Net-(IC2A-+IN)") (class "Default")
      (node (ref "C8") (pin "1") (pinfunction "1_1") (pintype "passive"))
      (node (ref "IC2") (pin "3") (pinfunction "+IN_3") (pintype "input"))
      (node (ref "R24") (pin "2") (pinfunction "2_2") (pintype "passive"))
    )
    (net (code "34") (name "Net-(IC2A--IN)") (class "Default")
      (node (ref "C9") (pin "1") (pinfunction "1_1") (pintype "passive"))
      (node (ref "IC2") (pin "2") (pinfunction "-IN_2") (pintype "input"))
      (node (ref "IC7") (pin "3") (pinfunction "X_3") (pintype "bidirectional"))
      (node (ref "R25") (pin "2") (pinfunction "2_2") (pintype "passive"))
    )
    (net (code "35") (name "Net-(IC2B-+IN)") (class "Default")
      (node (ref "C17") (pin "1") (pinfunction "1_1") (pintype "passive"))
      (node (ref "IC2") (pin "5") (pinfunction "+IN_5") (pintype "input"))
      (node (ref "R1") (pin "2") (pinfunction "2_2") (pintype "passive"))
    )
    (net (code "36") (name "Net-(IC2B--IN)") (class "Default")
      (node (ref "C18") (pin "1") (pinfunction "1_1") (pintype "passive"))
      (node (ref "IC2") (pin "6") (pinfunction "-IN_6") (pintype "input"))
      (node (ref "R17") (pin "2") (pinfunction "2_2") (pintype "passive"))
      (node (ref "R20") (pin "2") (pinfunction "2_2") (pintype "passive"))
    )
    (net (code "37") (name "Net-(IC2B-OUT)") (class "Default")
      (node (ref "C18") (pin "2") (pinfunction "2_2") (pintype "passive"))
      (node (ref "C8") (pin "2") (pinfunction "2_2") (pintype "passive"))
      (node (ref "IC2") (pin "7") (pinfunction "OUT_7") (pintype "output"))
      (node (ref "R17") (pin "1") (pinfunction "1_1") (pintype "passive"))
    )
    (net (code "38") (name "Net-(IC7A-INH)") (class "Default")
      (node (ref "IC7") (pin "6") (pinfunction "INH_6") (pintype "input"))
      (node (ref "R37") (pin "2") (pinfunction "2_2") (pintype "passive"))
    )
    (net (code "39") (name "Net-(IC7A-X0)") (class "Default")
      (node (ref "IC7") (pin "13") (pinfunction "X0_13") (pintype "bidirectional"))
      (node (ref "R27") (pin "2") (pinfunction "2_2") (pintype "passive"))
    )
    (net (code "40") (name "Net-(IC7A-X1)") (class "Default")
      (node (ref "IC7") (pin "14") (pinfunction "X1_14") (pintype "bidirectional"))
      (node (ref "R28") (pin "2") (pinfunction "2_2") (pintype "passive"))
    )
    (net (code "41") (name "Net-(IC7A-X2)") (class "Default")
      (node (ref "IC7") (pin "15") (pinfunction "X2_15") (pintype "bidirectional"))
      (node (ref "R29") (pin "2") (pinfunction "2_2") (pintype "passive"))
    )
    (net (code "42") (name "Net-(IC7A-X3)") (class "Default")
      (node (ref "IC7") (pin "12") (pinfunction "X3_12") (pintype "bidirectional"))
      (node (ref "R30") (pin "2") (pinfunction "2_2") (pintype "passive"))
    )
    (net (code "43") (name "Net-(T1-B)") (class "Default")
      (node (ref "R11") (pin "2") (pinfunction "2_2") (pintype "passive"))
      (node (ref "T1") (pin "1") (pinfunction "B_1") (pintype "passive"))
    )
    (net (code "44") (name "Net-(T2-B)") (class "Default")
      (node (ref "R2") (pin "2") (pinfunction "2_2") (pintype "passive"))
      (node (ref "T2") (pin "1") (pinfunction "B_1") (pintype "passive"))
    )
    (net (code "45") (name "Net-(T3-B)") (class "Default")
      (node (ref "R13") (pin "2") (pinfunction "2_2") (pintype "passive"))
      (node (ref "T3") (pin "1") (pinfunction "B_1") (pintype "passive"))
    )
    (net (code "46") (name "Net-(T4-B)") (class "Default")
      (node (ref "R9") (pin "2") (pinfunction "2_2") (pintype "passive"))
      (node (ref "T4") (pin "1") (pinfunction "B_1") (pintype "passive"))
    )
    (net (code "47") (name "Net-(T5-B)") (class "Default")
      (node (ref "R7") (pin "2") (pinfunction "2_2") (pintype "passive"))
      (node (ref "T5") (pin "1") (pinfunction "B_1") (pintype "passive"))
    )
    (net (code "48") (name "Net-(U1-ADDR)") (class "Default")
      (node (ref "R42") (pin "1") (pinfunction "1_1") (pintype "passive"))
      (node (ref "U1") (pin "1") (pinfunction "ADDR_1") (pintype "bidirectional"))
    )
    (net (code "49") (name "PHOTODIODE_1_ADC") (class "Default")
      (node (ref "C17") (pin "2") (pinfunction "2_2") (pintype "passive"))
      (node (ref "C20") (pin "2") (pinfunction "2_2") (pintype "passive"))
      (node (ref "C4") (pin "2") (pinfunction "2_2") (pintype "passive"))
      (node (ref "IC1") (pin "1") (pinfunction "OUT_1") (pintype "output"))
      (node (ref "R12") (pin "2") (pinfunction "2_2") (pintype "passive"))
      (node (ref "U1") (pin "5") (pinfunction "AIN1_5") (pintype "bidirectional"))
    )
    (net (code "50") (name "PHOTODIODE_2_ADC") (class "Default")
      (node (ref "PAD9") (pin "1") (pinfunction "P_1") (pintype "passive"))
      (node (ref "U1") (pin "7") (pinfunction "AIN3_7") (pintype "bidirectional"))
    )
    (net (code "51") (name "PHOTO_TRANS_COLLECTOR") (class "Default")
      (node (ref "C4") (pin "1") (pinfunction "1_1") (pintype "passive"))
      (node (ref "IC1") (pin "2") (pinfunction "-IN_2") (pintype "input"))
      (node (ref "R12") (pin "1") (pinfunction "1_1") (pintype "passive"))
      (node (ref "XR1") (pin "COLL") (pinfunction "CO_COLL") (pintype "passive"))
    )
    (net (code "52") (name "PPG_SIGNAL_1_ADC") (class "Default")
      (node (ref "C9") (pin "2") (pinfunction "2_2") (pintype "passive"))
      (node (ref "IC2") (pin "1") (pinfunction "OUT_1") (pintype "output"))
      (node (ref "R25") (pin "1") (pinfunction "1_1") (pintype "passive"))
      (node (ref "U1") (pin "6") (pinfunction "AIN2_6") (pintype "bidirectional"))
    )
    (net (code "53") (name "PPG_SIGNAL_2_ADC") (class "Default")
      (node (ref "C19") (pin "2") (pinfunction "2_2") (pintype "passive"))
      (node (ref "R22") (pin "2") (pinfunction "2_2") (pintype "passive"))
      (node (ref "U1") (pin "4") (pinfunction "AIN0_4") (pintype "bidirectional"))
    )
    (net (code "54") (name "PPG_SIGNAL_GAIN_A") (class "Default")
      (node (ref "IC7") (pin "11") (pinfunction "A_11") (pintype "input"))
      (node (ref "U3") (pin "13") (pinfunction "IO14_13") (pintype "bidirectional"))
    )
    (net (code "55") (name "PPG_SIGNAL_GAIN_B") (class "Default")
      (node (ref "IC7") (pin "10") (pinfunction "B_10") (pintype "input"))
      (node (ref "U3") (pin "12") (pinfunction "IO27_12") (pintype "bidirectional"))
    )
    (net (code "56") (name "RTS") (class "Default")
      (node (ref "PAD15") (pin "1") (pinfunction "P_1") (pintype "passive"))
      (node (ref "R11") (pin "1") (pinfunction "1_1") (pintype "passive"))
      (node (ref "T2") (pin "2") (pinfunction "E_2") (pintype "passive"))
    )
    (net (code "57") (name "R_PROG") (class "Default")
      (node (ref "IC5") (pin "2") (pinfunction "PROG_2") (pintype "bidirectional"))
      (node (ref "R3") (pin "2") (pinfunction "2_2") (pintype "passive"))
    )
    (net (code "58") (name "SCL") (class "Default")
      (node (ref "PAD3") (pin "1") (pinfunction "P_1") (pintype "passive"))
      (node (ref "R43") (pin "1") (pinfunction "1_1") (pintype "passive"))
      (node (ref "U1") (pin "10") (pinfunction "SCL_10") (pintype "bidirectional"))
      (node (ref "U3") (pin "36") (pinfunction "IO22_36") (pintype "bidirectional"))
    )
    (net (code "59") (name "SDA") (class "Default")
      (node (ref "PAD4") (pin "1") (pinfunction "P_1") (pintype "passive"))
      (node (ref "R44") (pin "1") (pinfunction "1_1") (pintype "passive"))
      (node (ref "U1") (pin "9") (pinfunction "SDA_9") (pintype "bidirectional"))
      (node (ref "U3") (pin "33") (pinfunction "IO21_33") (pintype "bidirectional"))
    )
    (net (code "60") (name "VIN") (class "Default")
      (node (ref "C1") (pin "1") (pinfunction "1_1") (pintype "passive"))
      (node (ref "IC8") (pin "2") (pinfunction "IN_2") (pintype "input"))
      (node (ref "PAD20") (pin "1") (pinfunction "P_1") (pintype "passive"))
    )
    (net (code "61") (name "VIN_SW") (class "Default")
      (node (ref "D1") (pin "C") (pinfunction "C_C") (pintype "passive"))
      (node (ref "PAD19") (pin "1") (pinfunction "P_1") (pintype "passive"))
      (node (ref "Q5") (pin "2") (pinfunction "S_2") (pintype "passive"))
    )
    (net (code "62") (name "V_BATT") (class "Default")
      (node (ref "C14") (pin "1") (pinfunction "1_1") (pintype "passive"))
      (node (ref "IC5") (pin "5") (pinfunction "BAT_5") (pintype "bidirectional"))
      (node (ref "PAD1") (pin "1") (pinfunction "P_1") (pintype "passive"))
      (node (ref "Q5") (pin "3") (pinfunction "D_3") (pintype "passive"))
      (node (ref "R16") (pin "2") (pinfunction "2_2") (pintype "passive"))
    )
    (net (code "63") (name "V_BATT_ADC") (class "Default")
      (node (ref "C16") (pin "1") (pinfunction "1_1") (pintype "passive"))
      (node (ref "R15") (pin "2") (pinfunction "2_2") (pintype "passive"))
      (node (ref "R16") (pin "1") (pinfunction "1_1") (pintype "passive"))
      (node (ref "U3") (pin "7") (pinfunction "IO35_7") (pintype "bidirectional"))
    )
    (net (code "64") (name "V_USB") (class "Default")
      (node (ref "C2") (pin "1") (pinfunction "1_1") (pintype "passive"))
      (node (ref "C3") (pin "1") (pinfunction "1_1") (pintype "passive"))
      (node (ref "C7") (pin "1") (pinfunction "1_1") (pintype "passive"))
      (node (ref "D1") (pin "A") (pinfunction "A_A") (pintype "passive"))
      (node (ref "D3") (pin "A") (pinfunction "A_A") (pintype "passive"))
      (node (ref "D4") (pin "A") (pinfunction "A_A") (pintype "passive"))
      (node (ref "IC5") (pin "4") (pinfunction "VCC_4") (pintype "bidirectional"))
      (node (ref "PAD25") (pin "1") (pinfunction "P_1") (pintype "passive"))
      (node (ref "Q5") (pin "1") (pinfunction "G_1") (pintype "passive"))
      (node (ref "R10") (pin "2") (pinfunction "2_2") (pintype "passive"))
      (node (ref "R14") (pin "1") (pinfunction "1_1") (pintype "passive"))
      (node (ref "R35") (pin "2") (pinfunction "2_2") (pintype "passive"))
      (node (ref "R40") (pin "2") (pinfunction "2_2") (pintype "passive"))
      (node (ref "U$1") (pin "1") (pinfunction "1_1") (pintype "input"))
    )
    (net (code "65") (name "V_USB_ADC") (class "Default")
      (node (ref "C15") (pin "1") (pinfunction "1_1") (pintype "passive"))
      (node (ref "R26") (pin "2") (pinfunction "2_2") (pintype "passive"))
      (node (ref "R35") (pin "1") (pinfunction "1_1") (pintype "passive"))
      (node (ref "U3") (pin "6") (pinfunction "IO34_6") (pintype "bidirectional"))
    )
    (net (code "66") (name "unconnected-(IC7A-X4-Pad1)") (class "Default")
      (node (ref "IC7") (pin "1") (pinfunction "X4_1") (pintype "bidirectional"))
    )
    (net (code "67") (name "unconnected-(IC7A-X5-Pad5)") (class "Default")
      (node (ref "IC7") (pin "5") (pinfunction "X5_5") (pintype "bidirectional"))
    )
    (net (code "68") (name "unconnected-(IC7A-X6-Pad2)") (class "Default")
      (node (ref "IC7") (pin "2") (pinfunction "X6_2") (pintype "bidirectional"))
    )
    (net (code "69") (name "unconnected-(IC7A-X7-Pad4)") (class "Default")
      (node (ref "IC7") (pin "4") (pinfunction "X7_4") (pintype "bidirectional"))
    )
    (net (code "70") (name "unconnected-(U$1-GND1-PadP$1)") (class "Default")
      (node (ref "U$1") (pin "P$1") (pinfunction "GND1_P$1") (pintype "bidirectional"))
    )
    (net (code "71") (name "unconnected-(U$1-GND2-PadP$2)") (class "Default")
      (node (ref "U$1") (pin "P$2") (pinfunction "GND2_P$2") (pintype "bidirectional"))
    )
    (net (code "72") (name "unconnected-(U$1-Pad2)") (class "Default")
      (node (ref "U$1") (pin "2") (pinfunction "2_2") (pintype "input"))
    )
    (net (code "73") (name "unconnected-(U$1-Pad3)") (class "Default")
      (node (ref "U$1") (pin "3") (pinfunction "3_3") (pintype "input"))
    )
    (net (code "74") (name "unconnected-(U$1-Pad4)") (class "Default")
      (node (ref "U$1") (pin "4") (pinfunction "4_4") (pintype "input"))
    )
    (net (code "75") (name "unconnected-(U3-IO2-Pad24)") (class "Default")
      (node (ref "U3") (pin "24") (pinfunction "IO2_24") (pintype "bidirectional"))
    )
    (net (code "76") (name "unconnected-(U3-IO12-Pad14)") (class "Default")
      (node (ref "U3") (pin "14") (pinfunction "IO12_14") (pintype "bidirectional"))
    )
    (net (code "77") (name "unconnected-(U3-SCL{slash}CLK-Pad20)") (class "Default")
      (node (ref "U3") (pin "20") (pinfunction "SCL/CLK_20") (pintype "bidirectional"))
    )
    (net (code "78") (name "unconnected-(U3-SCS{slash}CMD-Pad19)") (class "Default")
      (node (ref "U3") (pin "19") (pinfunction "SCS/CMD_19") (pintype "bidirectional"))
    )
    (net (code "79") (name "unconnected-(U3-SDI{slash}SD1-Pad22)") (class "Default")
      (node (ref "U3") (pin "22") (pinfunction "SDI/SD1_22") (pintype "bidirectional"))
    )
    (net (code "80") (name "unconnected-(U3-SDO{slash}SD0-Pad21)") (class "Default")
      (node (ref "U3") (pin "21") (pinfunction "SDO/SD0_21") (pintype "bidirectional"))
    )
    (net (code "81") (name "unconnected-(U3-SENSOR_VN-Pad5)") (class "Default")
      (node (ref "U3") (pin "5") (pinfunction "SENSOR_VN_5") (pintype "input"))
    )
    (net (code "82") (name "unconnected-(U3-SENSOR_VP-Pad4)") (class "Default")
      (node (ref "U3") (pin "4") (pinfunction "SENSOR_VP_4") (pintype "input"))
    )
    (net (code "83") (name "unconnected-(U3-SHD{slash}SD2-Pad17)") (class "Default")
      (node (ref "U3") (pin "17") (pinfunction "SHD/SD2_17") (pintype "bidirectional"))
    )
    (net (code "84") (name "unconnected-(U3-SWP{slash}SD3-Pad18)") (class "Default")
      (node (ref "U3") (pin "18") (pinfunction "SWP/SD3_18") (pintype "bidirectional"))
    )
  )
)
